# STM32.net
KiCad netlist of a schematic drawn in Altium Designer
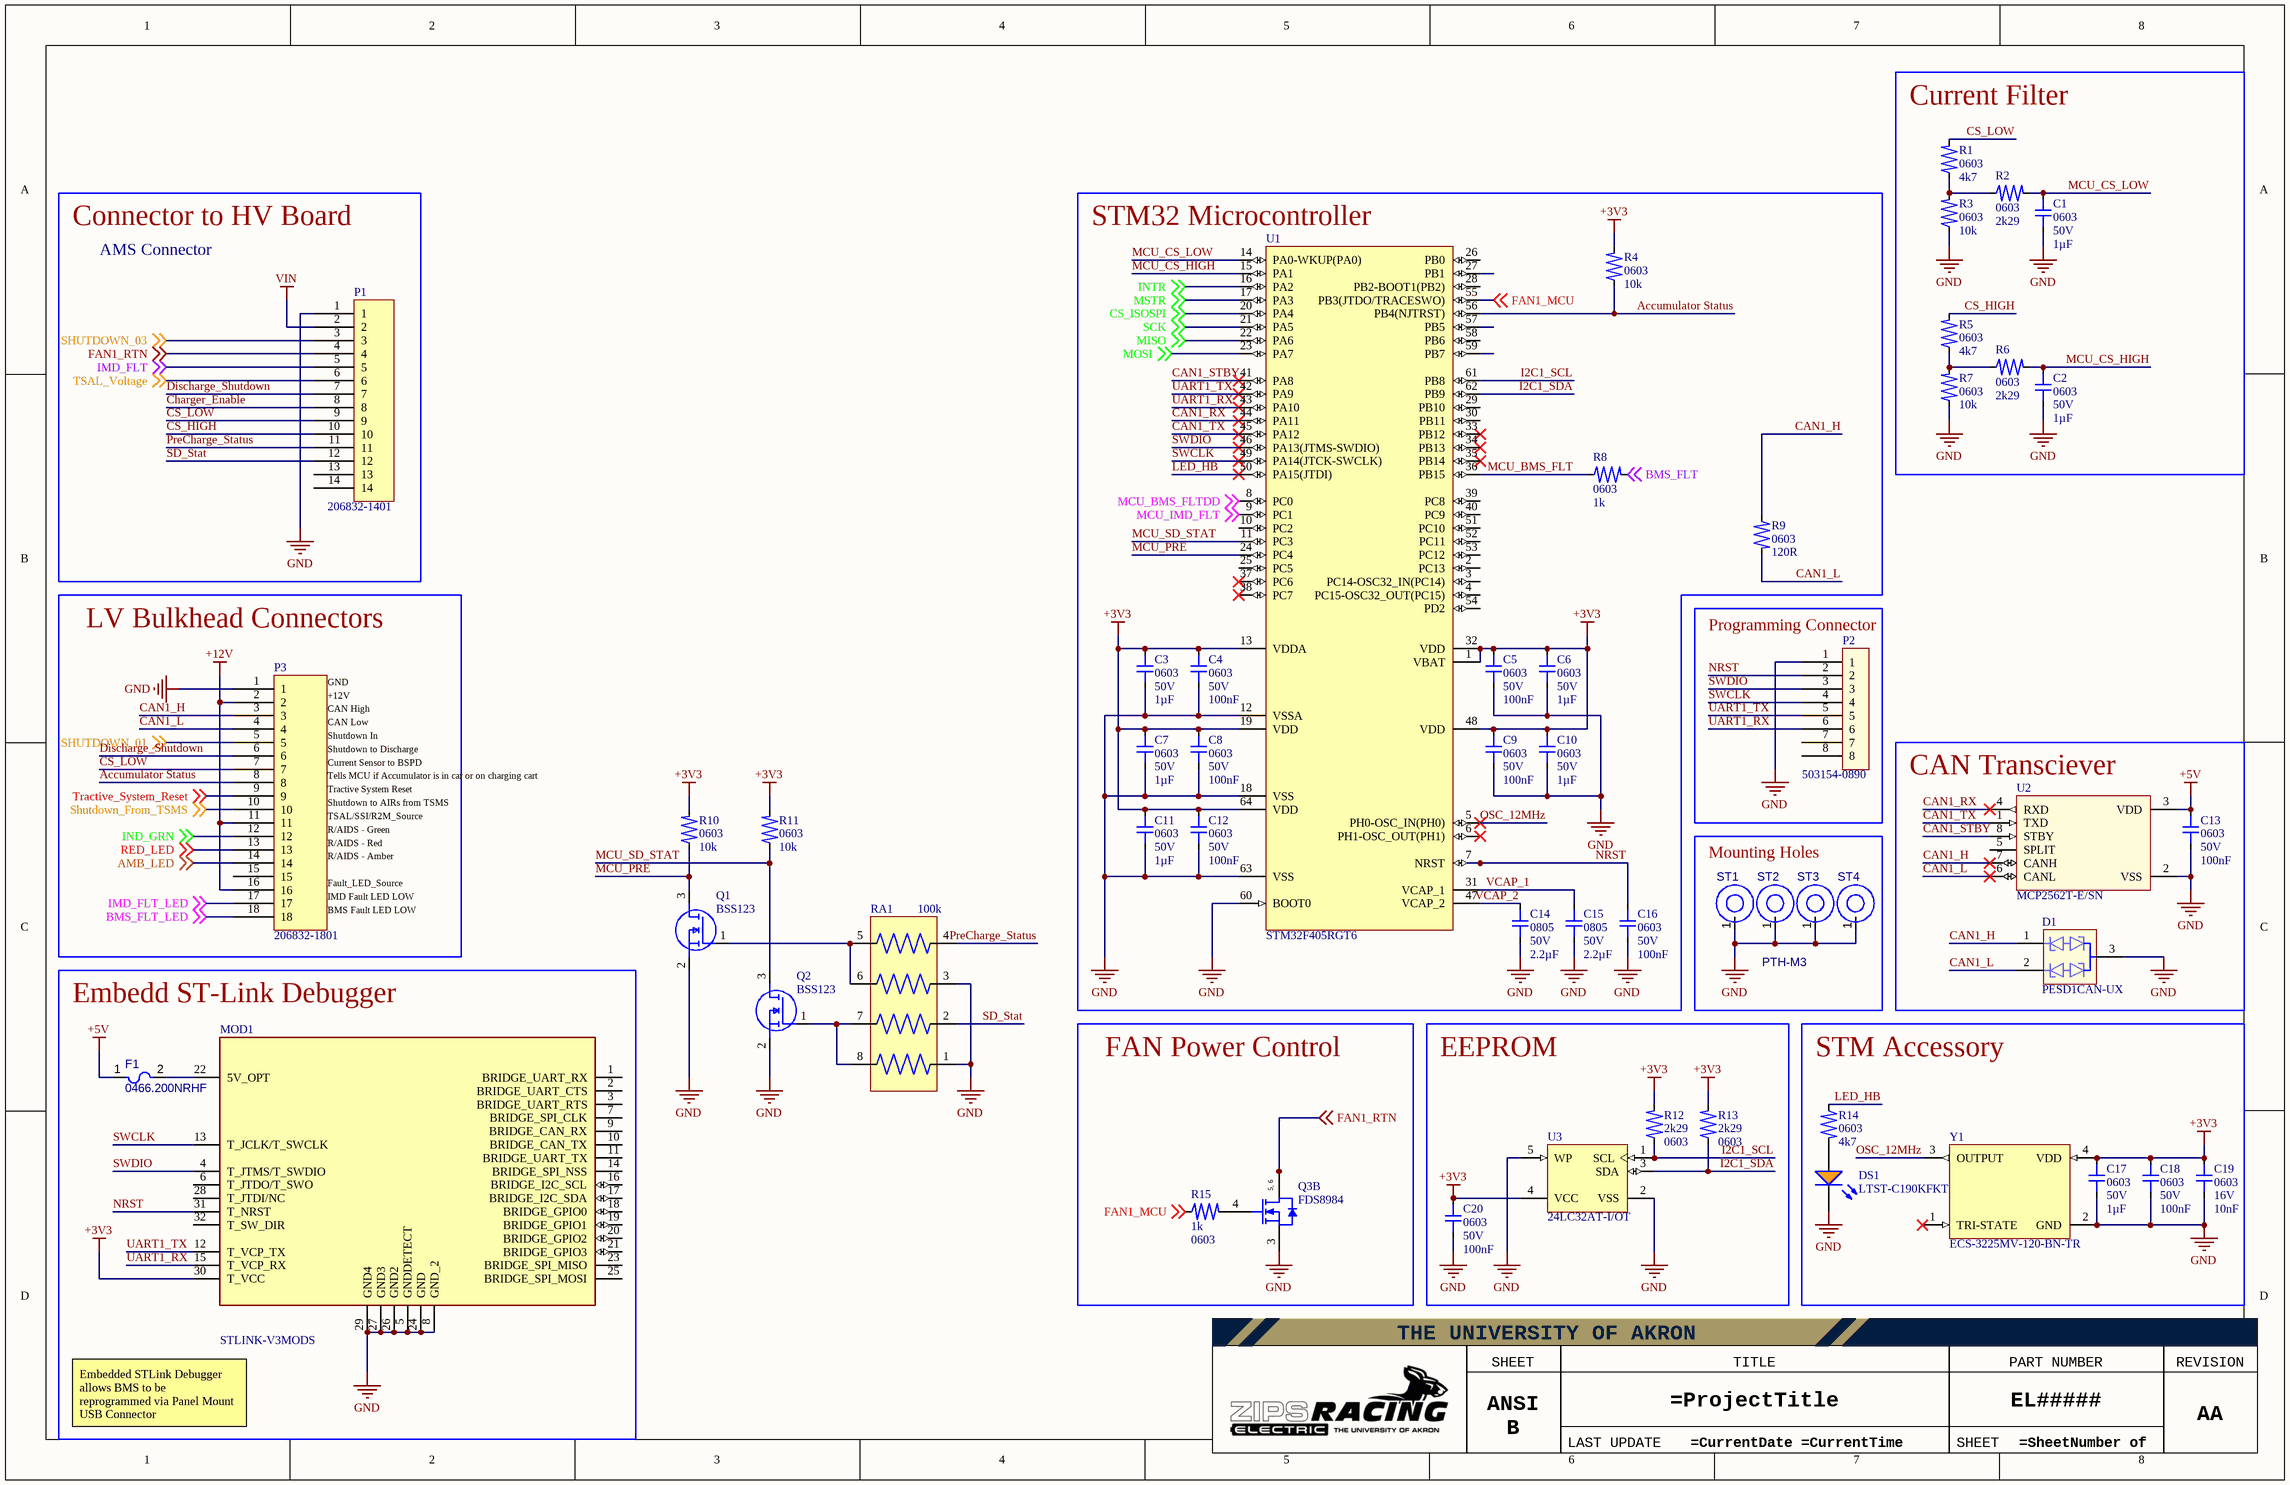
[diagram p0: STM32.SchDoc]

(export (version "E")
  (design (tool "Eeschema 10.0.6"))
  (components
    (comp (ref "C1")
      (value "1µF")
      (footprint "0603")
      (description "Capacitor, 0603, 5%")
      (fields (field (name "VOLTAGE") "50V") (field (name "Comment") "Capacitor 1uF 0603 5%"))
      (libsource (lib "Zips Racing Electric") (part "CAP-0603"))
    )
    (comp (ref "C2")
      (value "1µF")
      (footprint "0603")
      (description "Capacitor, 0603, 5%")
      (fields (field (name "VOLTAGE") "50V") (field (name "Comment") "Capacitor 1uF 0603 5%"))
      (libsource (lib "Zips Racing Electric") (part "CAP-0603"))
    )
    (comp (ref "C3")
      (value "1µF")
      (footprint "0603")
      (description "Capacitor, 0603, 5%")
      (fields (field (name "VOLTAGE") "50V") (field (name "Comment") "Capacitor 1uF 0603 5%"))
      (libsource (lib "Zips Racing Electric") (part "CAP-0603"))
    )
    (comp (ref "C4")
      (value "100nF")
      (footprint "0603")
      (description "Capacitor, 0603, 5%")
      (fields (field (name "VOLTAGE") "50V") (field (name "Comment") "Capacitor 100nF 0603 5%"))
      (libsource (lib "Zips Racing Electric") (part "CAP-0603"))
    )
    (comp (ref "C5")
      (value "100nF")
      (footprint "0603")
      (description "Capacitor, 0603, 5%")
      (fields (field (name "VOLTAGE") "50V") (field (name "Comment") "Capacitor 100nF 0603 5%"))
      (libsource (lib "Zips Racing Electric") (part "CAP-0603"))
    )
    (comp (ref "C6")
      (value "1µF")
      (footprint "0603")
      (description "Capacitor, 0603, 5%")
      (fields (field (name "VOLTAGE") "50V") (field (name "Comment") "Capacitor 1uF 0603 5%"))
      (libsource (lib "Zips Racing Electric") (part "CAP-0603"))
    )
    (comp (ref "C7")
      (value "1µF")
      (footprint "0603")
      (description "Capacitor, 0603, 5%")
      (fields (field (name "VOLTAGE") "50V") (field (name "Comment") "Capacitor 1uF 0603 5%"))
      (libsource (lib "Zips Racing Electric") (part "CAP-0603"))
    )
    (comp (ref "C8")
      (value "100nF")
      (footprint "0603")
      (description "Capacitor, 0603, 5%")
      (fields (field (name "VOLTAGE") "50V") (field (name "Comment") "Capacitor 100nF 0603 5%"))
      (libsource (lib "Zips Racing Electric") (part "CAP-0603"))
    )
    (comp (ref "C9")
      (value "100nF")
      (footprint "0603")
      (description "Capacitor, 0603, 5%")
      (fields (field (name "VOLTAGE") "50V") (field (name "Comment") "Capacitor 100nF 0603 5%"))
      (libsource (lib "Zips Racing Electric") (part "CAP-0603"))
    )
    (comp (ref "C10")
      (value "1µF")
      (footprint "0603")
      (description "Capacitor, 0603, 5%")
      (fields (field (name "VOLTAGE") "50V") (field (name "Comment") "Capacitor 1uF 0603 5%"))
      (libsource (lib "Zips Racing Electric") (part "CAP-0603"))
    )
    (comp (ref "C11")
      (value "1µF")
      (footprint "0603")
      (description "Capacitor, 0603, 5%")
      (fields (field (name "VOLTAGE") "50V") (field (name "Comment") "Capacitor 1uF 0603 5%"))
      (libsource (lib "Zips Racing Electric") (part "CAP-0603"))
    )
    (comp (ref "C12")
      (value "100nF")
      (footprint "0603")
      (description "Capacitor, 0603, 5%")
      (fields (field (name "VOLTAGE") "50V") (field (name "Comment") "Capacitor 100nF 0603 5%"))
      (libsource (lib "Zips Racing Electric") (part "CAP-0603"))
    )
    (comp (ref "C13")
      (value "100nF")
      (footprint "0603")
      (description "Capacitor, 0603, 5%")
      (fields (field (name "VOLTAGE") "50V") (field (name "Comment") "Capacitor 100nF 0603 5%"))
      (libsource (lib "Zips Racing Electric") (part "CAP-0603"))
    )
    (comp (ref "C14")
      (value "2.2µF")
      (footprint "0805")
      (description "Capacitor, 0805, 5%")
      (fields (field (name "VOLTAGE") "50V") (field (name "Comment") "Capacitor 2.2F 0805 5%"))
      (libsource (lib "Zips Racing Electric") (part "CAP-0603"))
    )
    (comp (ref "C15")
      (value "2.2µF")
      (footprint "0805")
      (description "Capacitor, 0805, 5%")
      (fields (field (name "VOLTAGE") "50V") (field (name "Comment") "Capacitor 2.2F 0805 5%"))
      (libsource (lib "Zips Racing Electric") (part "CAP-0603"))
    )
    (comp (ref "C16")
      (value "100nF")
      (footprint "0603")
      (description "Capacitor, 0603, 5%")
      (fields (field (name "VOLTAGE") "50V") (field (name "Comment") "Capacitor 100nF 0603 5%"))
      (libsource (lib "Zips Racing Electric") (part "CAP-0603"))
    )
    (comp (ref "C17")
      (value "1µF")
      (footprint "0603")
      (description "Capacitor, 0603, 5%")
      (fields (field (name "VOLTAGE") "50V") (field (name "Comment") "Capacitor 1uF 0603 5%"))
      (libsource (lib "Zips Racing Electric") (part "CAP-0603"))
    )
    (comp (ref "C18")
      (value "100nF")
      (footprint "0603")
      (description "Capacitor, 0603, 5%")
      (fields (field (name "VOLTAGE") "50V") (field (name "Comment") "Capacitor 100nF 0603 5%"))
      (libsource (lib "Zips Racing Electric") (part "CAP-0603"))
    )
    (comp (ref "C19")
      (value "10nF")
      (footprint "0603")
      (description "Capacitor, 0603, 5%")
      (fields (field (name "VOLTAGE") "16V") (field (name "Comment") "Capacitor 10nF 0603 5%"))
      (libsource (lib "Zips Racing Electric") (part "CAP-0603"))
    )
    (comp (ref "C20")
      (value "100nF")
      (footprint "0603")
      (description "Capacitor, 0603, 5%")
      (fields (field (name "VOLTAGE") "50V") (field (name "Comment") "Capacitor 100nF 0603 5%"))
      (libsource (lib "Zips Racing Electric") (part "CAP-0603"))
    )
    (comp (ref "D1")
      (value "PESD1CAN-UX")
      (footprint "FP-SOT323-MFG")
      (description "Trans Voltage Suppressor Diode, 150W, 24V V(RWM), Bidirectional, 2 Element, Silicon")
      (libsource (lib "Zips Racing Electric") (part "04d57993b6b7b0f5b3c95ba4f97dea0"))
    )
    (comp (ref "DS1")
      (value "LTST-C190KFKT")
      (footprint "LTST-C190KFKT_V")
      (description "LED Uni-Color Orange, 75 mW, 30 mA, -35 to 85 degC, 2-Pin SMD, RoHS, Tape and Reel")
      (fields (field (name "POWER") "75mW") (field (name "MANUFACTURER") "Lite-On"))
      (libsource (lib "Zips Racing Electric") (part "LED-ORANGE-AK-2"))
    )
    (comp (ref "F1")
      (value "0466.200NRHF")
      (footprint "FP-0466-MFG")
      (description "Electric Fuse, Very Fast Blow, 0.2A, 125VAC, 125VDC, 50A (IR), Supplemental, Surface Mount, 1206")
      (libsource (lib "Zips Racing Electric") (part "FUSE-2"))
    )
    (comp (ref "MOD1")
      (value "STLINK-V3MODS")
      (footprint "STLINK-V3MODS-Footprint-1")
      (description "STLINK V3 Debugger Board Module")
      (libsource (lib "Zips Racing Electric") (part "STLINK-V3MODS-Symbol-1"))
    )
    (comp (ref "P1")
      (value "206832-1401")
      (footprint "206832-1001-Footprint-1")
      (description "MICRO-FIT Plus Header Assembly Dual Row 10 Position Straight Tin")
      (libsource (lib "Zips Racing Electric") (part "206832-1401-Symbol-1"))
    )
    (comp (ref "P2")
      (value "503154-0890")
      (footprint "FP-503154-0890-MFG")
      (libsource (lib "Zips Racing Electric") (part "503154-0890-Symbol-1"))
    )
    (comp (ref "P3")
      (value "206832-1801")
      (footprint "MOLEX_2068321801")
      (libsource (lib "Zips Racing Electric") (part "206832-1801"))
    )
    (comp (ref "Q1")
      (value "BSS123")
      (footprint "SOT96P237X111-3N")
      (description "MOSFET N-CH 100V 170MA SOT23-3")
      (fields
        (field (name "MOUSER PART NUMBER") "512-BSS123")
        (field (name "SOURCE") "Zips_Racing_Electric.SchLib")
      )
      (libsource (lib "Zips Racing Electric") (part "BSS123"))
    )
    (comp (ref "Q2")
      (value "BSS123")
      (footprint "SOT96P237X111-3N")
      (description "MOSFET N-CH 100V 170MA SOT23-3")
      (fields
        (field (name "MOUSER PART NUMBER") "512-BSS123")
        (field (name "SOURCE") "Zips_Racing_Electric.SchLib")
      )
      (libsource (lib "Zips Racing Electric") (part "BSS123"))
    )
    (comp (ref "Q3")
      (value "FDS8984")
      (footprint "FAIR-SOIC-8_V")
      (libsource (lib "Zips Racing Electric") (part "NEMOS-SGDD-SGDD-8"))
    )
    (comp (ref "R1")
      (value "4k7")
      (footprint "0603")
      (description "Resistor, 0603, 1%, 1/10W")
      (fields (field (name "TOLERANCE") "1%") (field (name "POWER") "100mW"))
      (libsource (lib "Zips Racing Electric") (part "RES-0603"))
    )
    (comp (ref "R2")
      (value "2k29")
      (footprint "0603")
      (description "Resistor, 0603, 1%, 1/10W")
      (fields (field (name "TOLERANCE") "1%") (field (name "POWER") "100mW"))
      (libsource (lib "Zips Racing Electric") (part "RES-0603"))
    )
    (comp (ref "R3")
      (value "10k")
      (footprint "0603")
      (description "Resistor, 0603, 10k")
      (fields (field (name "TOLERANCE") "1%") (field (name "POWER") "100mW"))
      (libsource (lib "Zips Racing Electric") (part "RES-0603"))
    )
    (comp (ref "R4")
      (value "10k")
      (footprint "0603")
      (description "Resistor, 0603, 10k")
      (fields (field (name "TOLERANCE") "1%") (field (name "POWER") "100mW"))
      (libsource (lib "Zips Racing Electric") (part "RES-0603"))
    )
    (comp (ref "R5")
      (value "4k7")
      (footprint "0603")
      (description "Resistor, 0603, 1%, 1/10W")
      (fields (field (name "TOLERANCE") "1%") (field (name "POWER") "100mW"))
      (libsource (lib "Zips Racing Electric") (part "RES-0603"))
    )
    (comp (ref "R6")
      (value "2k29")
      (footprint "0603")
      (description "Resistor, 0603, 1%, 1/10W")
      (fields (field (name "TOLERANCE") "1%") (field (name "POWER") "100mW"))
      (libsource (lib "Zips Racing Electric") (part "RES-0603"))
    )
    (comp (ref "R7")
      (value "10k")
      (footprint "0603")
      (description "Resistor, 0603, 10k")
      (fields (field (name "TOLERANCE") "1%") (field (name "POWER") "100mW"))
      (libsource (lib "Zips Racing Electric") (part "RES-0603"))
    )
    (comp (ref "R8")
      (value "1k")
      (footprint "0603")
      (description "Resistor, 0603, 1k")
      (fields (field (name "POWER") "100mW") (field (name "TOLERANCE") "1%"))
      (libsource (lib "Zips Racing Electric") (part "RES-0603"))
    )
    (comp (ref "R9")
      (value "120R")
      (footprint "0603")
      (description "Resistor, 0603, 1%, 1/10W")
      (fields (field (name "TOLERANCE") "1%") (field (name "POWER") "100mW"))
      (libsource (lib "Zips Racing Electric") (part "RES-0603"))
    )
    (comp (ref "R10")
      (value "10k")
      (footprint "0603")
      (description "Resistor, 0603, 10k")
      (fields (field (name "TOLERANCE") "1%") (field (name "POWER") "100mW"))
      (libsource (lib "Zips Racing Electric") (part "RES-0603"))
    )
    (comp (ref "R11")
      (value "10k")
      (footprint "0603")
      (description "Resistor, 0603, 10k")
      (fields (field (name "TOLERANCE") "1%") (field (name "POWER") "100mW"))
      (libsource (lib "Zips Racing Electric") (part "RES-0603"))
    )
    (comp (ref "R12")
      (value "2k29")
      (footprint "0603")
      (description "Resistor, 0603, 1%, 1/10W")
      (fields (field (name "TOLERANCE") "1%") (field (name "POWER") "100mW"))
      (libsource (lib "Zips Racing Electric") (part "RES-0603"))
    )
    (comp (ref "R13")
      (value "2k29")
      (footprint "0603")
      (description "Resistor, 0603, 1%, 1/10W")
      (fields (field (name "TOLERANCE") "1%") (field (name "POWER") "100mW"))
      (libsource (lib "Zips Racing Electric") (part "RES-0603"))
    )
    (comp (ref "R14")
      (value "4k7")
      (footprint "0603")
      (description "Resistor, 0603, 1%, 1/10W")
      (fields (field (name "TOLERANCE") "1%") (field (name "POWER") "100mW"))
      (libsource (lib "Zips Racing Electric") (part "RES-0603"))
    )
    (comp (ref "R15")
      (value "1k")
      (footprint "0603")
      (description "Resistor, 0603, 1k")
      (fields (field (name "POWER") "100mW") (field (name "TOLERANCE") "1%"))
      (libsource (lib "Zips Racing Electric") (part "RES-0603"))
    )
    (comp (ref "RA1")
      (value "100k")
      (footprint "New footprint 1")
      (fields (field (name "TOLERANCE") "5%") (field (name "Comment") "YC164-JR-07100KL"))
      (libsource (lib "Zips Racing Electric") (part "YC164-JR-07100KL-Symbol-1"))
    )
    (comp (ref "ST1")
      (value "PTH-M3")
      (footprint "PTH-M2D5X5")
      (description "M3 Plated Thru-Hole  (3.2mm), 7mm pad, 10 mm keep out zone")
      (libsource (lib "Zips Racing Electric") (part "CMP-00028-00000-1"))
    )
    (comp (ref "ST2")
      (value "PTH-M3")
      (footprint "PTH-M2D5X5")
      (description "M3 Plated Thru-Hole  (3.2mm), 7mm pad, 10 mm keep out zone")
      (libsource (lib "Zips Racing Electric") (part "CMP-00028-00000-1"))
    )
    (comp (ref "ST3")
      (value "PTH-M3")
      (footprint "PTH-M2D5X5")
      (description "M3 Plated Thru-Hole  (3.2mm), 7mm pad, 10 mm keep out zone")
      (libsource (lib "Zips Racing Electric") (part "CMP-00028-00000-1"))
    )
    (comp (ref "ST4")
      (value "PTH-M3")
      (footprint "PTH-M2D5X5")
      (description "M3 Plated Thru-Hole  (3.2mm), 7mm pad, 10 mm keep out zone")
      (libsource (lib "Zips Racing Electric") (part "CMP-00028-00000-1"))
    )
    (comp (ref "U1")
      (value "STM32F405RGT6")
      (footprint "STM-LQFP64_V")
      (description "RISC Microcontroller, 32-Bit, FLASH, CORTEX-M4 CPU, 168MHz, CMOS, PQFP64")
      (libsource (lib "Zips Racing Electric") (part "MC-ARM-STM32F4X5-SQ64"))
    )
    (comp (ref "U2")
      (value "MCP2562T-E/SN")
      (footprint "MCP2562T-E_SN-Footprint-1")
      (description "IC TXRX CAN 8SOIC")
      (libsource (lib "Zips Racing Electric") (part "MCP2562T-E_SN-Symbol-1"))
    )
    (comp (ref "U3")
      (value "24LC32AT-I/OT")
      (footprint "SOT-23-OT5_L")
      (description "EEPROM, 4KX8, Serial, CMOS, PDSO5")
      (libsource (lib "Zips Racing Electric") (part "MEM-SEEPROM-24AA16-OT-5"))
    )
    (comp (ref "Y1")
      (value "ECS-3225MV-120-BN-TR")
      (footprint "ECS-3225MV-120-BN-TR-Footprint-1")
      (description "HCMOS Output Clock Oscillator, 12MHz Nom")
      (libsource (lib "Zips Racing Electric") (part "ECS-3225MV-120-BN-TR-Symbol-1"))
    )
  )
  (nets
    (net (code "1") (name "+3V3") (class "Default")
      (node (ref "C10") (pin "2") (pinfunction "2_2") (pintype "passive"))
      (node (ref "C11") (pin "2") (pinfunction "2_2") (pintype "passive"))
      (node (ref "C12") (pin "2") (pinfunction "2_2") (pintype "passive"))
      (node (ref "C17") (pin "2") (pinfunction "2_2") (pintype "passive"))
      (node (ref "C18") (pin "2") (pinfunction "2_2") (pintype "passive"))
      (node (ref "C19") (pin "2") (pinfunction "2_2") (pintype "passive"))
      (node (ref "C20") (pin "2") (pinfunction "2_2") (pintype "passive"))
      (node (ref "C3") (pin "2") (pinfunction "2_2") (pintype "passive"))
      (node (ref "C4") (pin "2") (pinfunction "2_2") (pintype "passive"))
      (node (ref "C5") (pin "2") (pinfunction "2_2") (pintype "passive"))
      (node (ref "C6") (pin "2") (pinfunction "2_2") (pintype "passive"))
      (node (ref "C7") (pin "2") (pinfunction "2_2") (pintype "passive"))
      (node (ref "C8") (pin "2") (pinfunction "2_2") (pintype "passive"))
      (node (ref "C9") (pin "2") (pinfunction "2_2") (pintype "passive"))
      (node (ref "MOD1") (pin "30") (pinfunction "T_VCC_30") (pintype "passive"))
      (node (ref "R10") (pin "2") (pinfunction "2_2") (pintype "passive"))
      (node (ref "R11") (pin "2") (pinfunction "2_2") (pintype "passive"))
      (node (ref "R12") (pin "2") (pinfunction "2_2") (pintype "passive"))
      (node (ref "R13") (pin "2") (pinfunction "2_2") (pintype "passive"))
      (node (ref "R4") (pin "2") (pinfunction "2_2") (pintype "passive"))
      (node (ref "U1") (pin "1") (pinfunction "VBAT_1") (pintype "power_in"))
      (node (ref "U1") (pin "13") (pinfunction "VDDA_13") (pintype "power_in"))
      (node (ref "U1") (pin "19") (pinfunction "VDD_19") (pintype "power_in"))
      (node (ref "U1") (pin "32") (pinfunction "VDD_32") (pintype "power_in"))
      (node (ref "U1") (pin "48") (pinfunction "VDD_48") (pintype "power_in"))
      (node (ref "U1") (pin "64") (pinfunction "VDD_64") (pintype "power_in"))
      (node (ref "U3") (pin "4") (pinfunction "VCC_4") (pintype "power_in"))
      (node (ref "Y1") (pin "4") (pinfunction "VDD_4") (pintype "input"))
    )
    (net (code "2") (name "+5V") (class "Default")
      (node (ref "C13") (pin "2") (pinfunction "2_2") (pintype "passive"))
      (node (ref "F1") (pin "1") (pinfunction "1_1") (pintype "passive"))
      (node (ref "U2") (pin "3") (pinfunction "VDD_3") (pintype "power_in"))
    )
    (net (code "3") (name "+12V") (class "Default")
      (node (ref "P3") (pin "11") (pinfunction "11_11") (pintype "passive"))
      (node (ref "P3") (pin "16") (pinfunction "16_16") (pintype "passive"))
      (node (ref "P3") (pin "2") (pinfunction "2_2") (pintype "passive"))
    )
    (net (code "4") (name "/Accumulator Status") (class "Default")
      (node (ref "P3") (pin "8") (pinfunction "8_8") (pintype "passive"))
      (node (ref "R4") (pin "1") (pinfunction "1_1") (pintype "passive"))
      (node (ref "U1") (pin "56") (pinfunction "PB4(NJTRST)_56") (pintype "bidirectional"))
    )
    (net (code "5") (name "/CAN1_H") (class "Default")
      (node (ref "D1") (pin "1") (pinfunction "cathode_1_1") (pintype "passive"))
      (node (ref "P3") (pin "3") (pinfunction "3_3") (pintype "passive"))
      (node (ref "R9") (pin "1") (pinfunction "1_1") (pintype "passive"))
      (node (ref "U2") (pin "7") (pinfunction "CANH_7") (pintype "bidirectional"))
    )
    (net (code "6") (name "/CAN1_L") (class "Default")
      (node (ref "D1") (pin "2") (pinfunction "cathode_2_2") (pintype "passive"))
      (node (ref "P3") (pin "4") (pinfunction "4_4") (pintype "passive"))
      (node (ref "R9") (pin "2") (pinfunction "2_2") (pintype "passive"))
      (node (ref "U2") (pin "6") (pinfunction "CANL_6") (pintype "bidirectional"))
    )
    (net (code "7") (name "/CAN1_RX") (class "Default")
      (node (ref "U1") (pin "44") (pinfunction "PA11_44") (pintype "bidirectional"))
      (node (ref "U2") (pin "4") (pinfunction "RXD_4") (pintype "output"))
    )
    (net (code "8") (name "/CAN1_STBY") (class "Default")
      (node (ref "U1") (pin "41") (pinfunction "PA8_41") (pintype "bidirectional"))
      (node (ref "U2") (pin "8") (pinfunction "STBY_8") (pintype "input"))
    )
    (net (code "9") (name "/CAN1_TX") (class "Default")
      (node (ref "U1") (pin "45") (pinfunction "PA12_45") (pintype "bidirectional"))
      (node (ref "U2") (pin "1") (pinfunction "TXD_1") (pintype "input"))
    )
    (net (code "10") (name "/CS_HIGH") (class "Default")
      (node (ref "P1") (pin "10") (pinfunction "10_10") (pintype "passive"))
      (node (ref "R5") (pin "2") (pinfunction "2_2") (pintype "passive"))
    )
    (net (code "11") (name "/CS_LOW") (class "Default")
      (node (ref "P1") (pin "9") (pinfunction "9_9") (pintype "passive"))
      (node (ref "P3") (pin "7") (pinfunction "7_7") (pintype "passive"))
      (node (ref "R1") (pin "2") (pinfunction "2_2") (pintype "passive"))
    )
    (net (code "12") (name "/Charger_Enable") (class "Default")
      (node (ref "P1") (pin "8") (pinfunction "8_8") (pintype "passive"))
    )
    (net (code "13") (name "/Discharge_Shutdown") (class "Default")
      (node (ref "P1") (pin "7") (pinfunction "7_7") (pintype "passive"))
      (node (ref "P3") (pin "6") (pinfunction "6_6") (pintype "passive"))
    )
    (net (code "14") (name "/I2C1_SCL") (class "Default")
      (node (ref "R12") (pin "1") (pinfunction "1_1") (pintype "passive"))
      (node (ref "U1") (pin "61") (pinfunction "PB8_61") (pintype "bidirectional"))
      (node (ref "U3") (pin "1") (pinfunction "SCL_1") (pintype "input"))
    )
    (net (code "15") (name "/I2C1_SDA") (class "Default")
      (node (ref "R13") (pin "1") (pinfunction "1_1") (pintype "passive"))
      (node (ref "U1") (pin "62") (pinfunction "PB9_62") (pintype "bidirectional"))
      (node (ref "U3") (pin "3") (pinfunction "SDA_3") (pintype "bidirectional"))
    )
    (net (code "16") (name "/LED_HB") (class "Default")
      (node (ref "R14") (pin "1") (pinfunction "1_1") (pintype "passive"))
      (node (ref "U1") (pin "50") (pinfunction "PA15(JTDI)_50") (pintype "bidirectional"))
    )
    (net (code "17") (name "/MCU_BMS_FLT") (class "Default")
      (node (ref "R8") (pin "1") (pinfunction "1_1") (pintype "passive"))
      (node (ref "U1") (pin "36") (pinfunction "PB15_36") (pintype "bidirectional"))
    )
    (net (code "18") (name "/MCU_CS_HIGH") (class "Default")
      (node (ref "C2") (pin "2") (pinfunction "2_2") (pintype "passive"))
      (node (ref "R6") (pin "2") (pinfunction "2_2") (pintype "passive"))
      (node (ref "U1") (pin "15") (pinfunction "PA1_15") (pintype "bidirectional"))
    )
    (net (code "19") (name "/MCU_CS_LOW") (class "Default")
      (node (ref "C1") (pin "2") (pinfunction "2_2") (pintype "passive"))
      (node (ref "R2") (pin "2") (pinfunction "2_2") (pintype "passive"))
      (node (ref "U1") (pin "14") (pinfunction "PA0-WKUP(PA0)_14") (pintype "bidirectional"))
    )
    (net (code "20") (name "/MCU_PRE") (class "Default")
      (node (ref "Q1") (pin "3") (pinfunction "D_3") (pintype "passive"))
      (node (ref "R10") (pin "1") (pinfunction "1_1") (pintype "passive"))
      (node (ref "U1") (pin "24") (pinfunction "PC4_24") (pintype "bidirectional"))
    )
    (net (code "21") (name "/MCU_SD_STAT") (class "Default")
      (node (ref "Q2") (pin "3") (pinfunction "D_3") (pintype "passive"))
      (node (ref "R11") (pin "1") (pinfunction "1_1") (pintype "passive"))
      (node (ref "U1") (pin "11") (pinfunction "PC3_11") (pintype "bidirectional"))
    )
    (net (code "22") (name "/NRST") (class "Default")
      (node (ref "C16") (pin "2") (pinfunction "2_2") (pintype "passive"))
      (node (ref "MOD1") (pin "31") (pinfunction "T_NRST_31") (pintype "passive"))
      (node (ref "P2") (pin "2") (pinfunction "2_2") (pintype "passive"))
      (node (ref "U1") (pin "7") (pinfunction "NRST_7") (pintype "bidirectional"))
    )
    (net (code "23") (name "/OSC_12MHz") (class "Default")
      (node (ref "U1") (pin "5") (pinfunction "PH0-OSC_IN(PH0)_5") (pintype "bidirectional"))
      (node (ref "Y1") (pin "3") (pinfunction "OUTPUT_3") (pintype "output"))
    )
    (net (code "24") (name "/PreCharge_Status") (class "Default")
      (node (ref "P1") (pin "11") (pinfunction "11_11") (pintype "passive"))
      (node (ref "RA1") (pin "4") (pinfunction "4_4") (pintype "passive"))
    )
    (net (code "25") (name "/SD_Stat") (class "Default")
      (node (ref "P1") (pin "12") (pinfunction "12_12") (pintype "passive"))
      (node (ref "RA1") (pin "2") (pinfunction "2_2") (pintype "passive"))
    )
    (net (code "26") (name "/SWCLK") (class "Default")
      (node (ref "MOD1") (pin "13") (pinfunction "T_JCLK/T_SWCLK_13") (pintype "passive"))
      (node (ref "P2") (pin "4") (pinfunction "4_4") (pintype "passive"))
      (node (ref "U1") (pin "49") (pinfunction "PA14(JTCK-SWCLK)_49") (pintype "bidirectional"))
    )
    (net (code "27") (name "/SWDIO") (class "Default")
      (node (ref "MOD1") (pin "4") (pinfunction "T_JTMS/T_SWDIO_4") (pintype "passive"))
      (node (ref "P2") (pin "3") (pinfunction "3_3") (pintype "passive"))
      (node (ref "U1") (pin "46") (pinfunction "PA13(JTMS-SWDIO)_46") (pintype "bidirectional"))
    )
    (net (code "28") (name "/UART1_RX") (class "Default")
      (node (ref "MOD1") (pin "15") (pinfunction "T_VCP_RX_15") (pintype "passive"))
      (node (ref "P2") (pin "6") (pinfunction "6_6") (pintype "passive"))
      (node (ref "U1") (pin "43") (pinfunction "PA10_43") (pintype "bidirectional"))
    )
    (net (code "29") (name "/UART1_TX") (class "Default")
      (node (ref "MOD1") (pin "12") (pinfunction "T_VCP_TX_12") (pintype "passive"))
      (node (ref "P2") (pin "5") (pinfunction "5_5") (pintype "passive"))
      (node (ref "U1") (pin "42") (pinfunction "PA9_42") (pintype "bidirectional"))
    )
    (net (code "30") (name "/VCAP_1") (class "Default")
      (node (ref "C15") (pin "2") (pinfunction "2_2") (pintype "passive"))
      (node (ref "U1") (pin "31") (pinfunction "VCAP_1_31") (pintype "power_in"))
    )
    (net (code "31") (name "/VCAP_2") (class "Default")
      (node (ref "C14") (pin "2") (pinfunction "2_2") (pintype "passive"))
      (node (ref "U1") (pin "47") (pinfunction "VCAP_2_47") (pintype "power_in"))
    )
    (net (code "32") (name "AMB_LED") (class "Default")
      (node (ref "P3") (pin "14") (pinfunction "14_14") (pintype "passive"))
    )
    (net (code "33") (name "BMS_FLT") (class "Default")
      (node (ref "R8") (pin "2") (pinfunction "2_2") (pintype "passive"))
    )
    (net (code "34") (name "BMS_FLT_LED") (class "Default")
      (node (ref "P3") (pin "18") (pinfunction "18_18") (pintype "passive"))
    )
    (net (code "35") (name "CS_ISOSPI") (class "Default")
      (node (ref "U1") (pin "20") (pinfunction "PA4_20") (pintype "bidirectional"))
    )
    (net (code "36") (name "FAN1_MCU") (class "Default")
      (node (ref "R15") (pin "1") (pinfunction "1_1") (pintype "passive"))
      (node (ref "U1") (pin "55") (pinfunction "PB3(JTDO/TRACESWO)_55") (pintype "bidirectional"))
    )
    (net (code "37") (name "FAN1_RTN") (class "Default")
      (node (ref "P1") (pin "4") (pinfunction "4_4") (pintype "passive"))
      (node (ref "Q3") (pin "5") (pinfunction "D2_5") (pintype "passive"))
      (node (ref "Q3") (pin "6") (pinfunction "D2_6") (pintype "passive"))
    )
    (net (code "38") (name "GND") (class "Default")
      (node (ref "C1") (pin "1") (pinfunction "1_1") (pintype "passive"))
      (node (ref "C10") (pin "1") (pinfunction "1_1") (pintype "passive"))
      (node (ref "C11") (pin "1") (pinfunction "1_1") (pintype "passive"))
      (node (ref "C12") (pin "1") (pinfunction "1_1") (pintype "passive"))
      (node (ref "C13") (pin "1") (pinfunction "1_1") (pintype "passive"))
      (node (ref "C14") (pin "1") (pinfunction "1_1") (pintype "passive"))
      (node (ref "C15") (pin "1") (pinfunction "1_1") (pintype "passive"))
      (node (ref "C16") (pin "1") (pinfunction "1_1") (pintype "passive"))
      (node (ref "C17") (pin "1") (pinfunction "1_1") (pintype "passive"))
      (node (ref "C18") (pin "1") (pinfunction "1_1") (pintype "passive"))
      (node (ref "C19") (pin "1") (pinfunction "1_1") (pintype "passive"))
      (node (ref "C2") (pin "1") (pinfunction "1_1") (pintype "passive"))
      (node (ref "C20") (pin "1") (pinfunction "1_1") (pintype "passive"))
      (node (ref "C3") (pin "1") (pinfunction "1_1") (pintype "passive"))
      (node (ref "C4") (pin "1") (pinfunction "1_1") (pintype "passive"))
      (node (ref "C5") (pin "1") (pinfunction "1_1") (pintype "passive"))
      (node (ref "C6") (pin "1") (pinfunction "1_1") (pintype "passive"))
      (node (ref "C7") (pin "1") (pinfunction "1_1") (pintype "passive"))
      (node (ref "C8") (pin "1") (pinfunction "1_1") (pintype "passive"))
      (node (ref "C9") (pin "1") (pinfunction "1_1") (pintype "passive"))
      (node (ref "D1") (pin "3") (pinfunction "common_cathode_3") (pintype "passive"))
      (node (ref "DS1") (pin "2") (pinfunction "K_2") (pintype "passive"))
      (node (ref "MOD1") (pin "24") (pinfunction "GND_24") (pintype "power_in"))
      (node (ref "MOD1") (pin "26") (pinfunction "GND2_26") (pintype "power_in"))
      (node (ref "MOD1") (pin "27") (pinfunction "GND3_27") (pintype "power_in"))
      (node (ref "MOD1") (pin "29") (pinfunction "GND4_29") (pintype "power_in"))
      (node (ref "MOD1") (pin "5") (pinfunction "GNDDETECT_5") (pintype "power_in"))
      (node (ref "MOD1") (pin "8") (pinfunction "GND_2_8") (pintype "power_in"))
      (node (ref "P1") (pin "1") (pinfunction "1_1") (pintype "passive"))
      (node (ref "P2") (pin "1") (pinfunction "1_1") (pintype "passive"))
      (node (ref "P3") (pin "1") (pinfunction "1_1") (pintype "passive"))
      (node (ref "Q1") (pin "2") (pinfunction "S_2") (pintype "passive"))
      (node (ref "Q2") (pin "2") (pinfunction "S_2") (pintype "passive"))
      (node (ref "Q3") (pin "3") (pinfunction "S2_3") (pintype "passive"))
      (node (ref "R3") (pin "1") (pinfunction "1_1") (pintype "passive"))
      (node (ref "R7") (pin "1") (pinfunction "1_1") (pintype "passive"))
      (node (ref "RA1") (pin "1") (pinfunction "1_1") (pintype "passive"))
      (node (ref "RA1") (pin "3") (pinfunction "3_3") (pintype "passive"))
      (node (ref "ST1") (pin "1") (pinfunction "H1_1") (pintype "passive"))
      (node (ref "ST2") (pin "1") (pinfunction "H1_1") (pintype "passive"))
      (node (ref "ST3") (pin "1") (pinfunction "H1_1") (pintype "passive"))
      (node (ref "ST4") (pin "1") (pinfunction "H1_1") (pintype "passive"))
      (node (ref "U1") (pin "12") (pinfunction "VSSA_12") (pintype "power_in"))
      (node (ref "U1") (pin "18") (pinfunction "VSS_18") (pintype "power_in"))
      (node (ref "U1") (pin "60") (pinfunction "BOOT0_60") (pintype "input"))
      (node (ref "U1") (pin "63") (pinfunction "VSS_63") (pintype "power_in"))
      (node (ref "U2") (pin "2") (pinfunction "VSS_2") (pintype "power_in"))
      (node (ref "U3") (pin "2") (pinfunction "VSS_2") (pintype "power_in"))
      (node (ref "U3") (pin "5") (pinfunction "WP_5") (pintype "input"))
      (node (ref "Y1") (pin "2") (pinfunction "GND_2") (pintype "power_in"))
    )
    (net (code "39") (name "IMD_FLT") (class "Default")
      (node (ref "P1") (pin "5") (pinfunction "5_5") (pintype "passive"))
    )
    (net (code "40") (name "IMD_FLT_LED") (class "Default")
      (node (ref "P3") (pin "17") (pinfunction "17_17") (pintype "passive"))
    )
    (net (code "41") (name "IND_GRN") (class "Default")
      (node (ref "P3") (pin "12") (pinfunction "12_12") (pintype "passive"))
    )
    (net (code "42") (name "INTR") (class "Default")
      (node (ref "U1") (pin "16") (pinfunction "PA2_16") (pintype "bidirectional"))
    )
    (net (code "43") (name "MCU_BMS_FLTDD") (class "Default")
      (node (ref "U1") (pin "8") (pinfunction "PC0_8") (pintype "bidirectional"))
    )
    (net (code "44") (name "MCU_IMD_FLT") (class "Default")
      (node (ref "U1") (pin "9") (pinfunction "PC1_9") (pintype "bidirectional"))
    )
    (net (code "45") (name "MISO") (class "Default")
      (node (ref "U1") (pin "22") (pinfunction "PA6_22") (pintype "bidirectional"))
    )
    (net (code "46") (name "MOSI") (class "Default")
      (node (ref "U1") (pin "23") (pinfunction "PA7_23") (pintype "bidirectional"))
    )
    (net (code "47") (name "MSTR") (class "Default")
      (node (ref "U1") (pin "17") (pinfunction "PA3_17") (pintype "bidirectional"))
    )
    (net (code "48") (name "Net-(DS1-A)") (class "Default")
      (node (ref "DS1") (pin "1") (pinfunction "A_1") (pintype "passive"))
      (node (ref "R14") (pin "2") (pinfunction "2_2") (pintype "passive"))
    )
    (net (code "49") (name "Net-(MOD1-5V_OPT)") (class "Default")
      (node (ref "F1") (pin "2") (pinfunction "2_2") (pintype "passive"))
      (node (ref "MOD1") (pin "22") (pinfunction "5V_OPT_22") (pintype "passive"))
    )
    (net (code "50") (name "Net-(Q1-G)") (class "Default")
      (node (ref "Q1") (pin "1") (pinfunction "G_1") (pintype "passive"))
      (node (ref "RA1") (pin "5") (pinfunction "5_5") (pintype "passive"))
      (node (ref "RA1") (pin "6") (pinfunction "6_6") (pintype "passive"))
    )
    (net (code "51") (name "Net-(Q2-G)") (class "Default")
      (node (ref "Q2") (pin "1") (pinfunction "G_1") (pintype "passive"))
      (node (ref "RA1") (pin "7") (pinfunction "7_7") (pintype "passive"))
      (node (ref "RA1") (pin "8") (pinfunction "8_8") (pintype "passive"))
    )
    (net (code "52") (name "Net-(Q3B-G2)") (class "Default")
      (node (ref "Q3") (pin "4") (pinfunction "G2_4") (pintype "passive"))
      (node (ref "R15") (pin "2") (pinfunction "2_2") (pintype "passive"))
    )
    (net (code "53") (name "Net-(R1-Pad1)") (class "Default")
      (node (ref "R1") (pin "1") (pinfunction "1_1") (pintype "passive"))
      (node (ref "R2") (pin "1") (pinfunction "1_1") (pintype "passive"))
      (node (ref "R3") (pin "2") (pinfunction "2_2") (pintype "passive"))
    )
    (net (code "54") (name "Net-(R5-Pad1)") (class "Default")
      (node (ref "R5") (pin "1") (pinfunction "1_1") (pintype "passive"))
      (node (ref "R6") (pin "1") (pinfunction "1_1") (pintype "passive"))
      (node (ref "R7") (pin "2") (pinfunction "2_2") (pintype "passive"))
    )
    (net (code "55") (name "RED_LED") (class "Default")
      (node (ref "P3") (pin "13") (pinfunction "13_13") (pintype "passive"))
    )
    (net (code "56") (name "SCK") (class "Default")
      (node (ref "U1") (pin "21") (pinfunction "PA5_21") (pintype "bidirectional"))
    )
    (net (code "57") (name "SHUTDOWN_01") (class "Default")
      (node (ref "P3") (pin "5") (pinfunction "5_5") (pintype "passive"))
    )
    (net (code "58") (name "SHUTDOWN_03") (class "Default")
      (node (ref "P1") (pin "3") (pinfunction "3_3") (pintype "passive"))
    )
    (net (code "59") (name "Shutdown_From_TSMS") (class "Default")
      (node (ref "P3") (pin "10") (pinfunction "10_10") (pintype "passive"))
    )
    (net (code "60") (name "TSAL_Voltage") (class "Default")
      (node (ref "P1") (pin "6") (pinfunction "6_6") (pintype "passive"))
    )
    (net (code "61") (name "Tractive_System_Reset") (class "Default")
      (node (ref "P3") (pin "9") (pinfunction "9_9") (pintype "passive"))
    )
    (net (code "62") (name "VIN") (class "Default")
      (node (ref "P1") (pin "2") (pinfunction "2_2") (pintype "passive"))
    )
    (net (code "63") (name "unconnected-(MOD1-BRIDGE_CAN_RX-Pad9)") (class "Default")
      (node (ref "MOD1") (pin "9") (pinfunction "BRIDGE_CAN_RX_9") (pintype "passive"))
    )
    (net (code "64") (name "unconnected-(MOD1-BRIDGE_CAN_TX-Pad10)") (class "Default")
      (node (ref "MOD1") (pin "10") (pinfunction "BRIDGE_CAN_TX_10") (pintype "passive"))
    )
    (net (code "65") (name "unconnected-(MOD1-BRIDGE_GPIO0-Pad18)") (class "Default")
      (node (ref "MOD1") (pin "18") (pinfunction "BRIDGE_GPIO0_18") (pintype "bidirectional"))
    )
    (net (code "66") (name "unconnected-(MOD1-BRIDGE_GPIO1-Pad19)") (class "Default")
      (node (ref "MOD1") (pin "19") (pinfunction "BRIDGE_GPIO1_19") (pintype "bidirectional"))
    )
    (net (code "67") (name "unconnected-(MOD1-BRIDGE_GPIO2-Pad20)") (class "Default")
      (node (ref "MOD1") (pin "20") (pinfunction "BRIDGE_GPIO2_20") (pintype "bidirectional"))
    )
    (net (code "68") (name "unconnected-(MOD1-BRIDGE_GPIO3-Pad21)") (class "Default")
      (node (ref "MOD1") (pin "21") (pinfunction "BRIDGE_GPIO3_21") (pintype "bidirectional"))
    )
    (net (code "69") (name "unconnected-(MOD1-BRIDGE_I2C_SCL-Pad16)") (class "Default")
      (node (ref "MOD1") (pin "16") (pinfunction "BRIDGE_I2C_SCL_16") (pintype "bidirectional"))
    )
    (net (code "70") (name "unconnected-(MOD1-BRIDGE_I2C_SDA-Pad17)") (class "Default")
      (node (ref "MOD1") (pin "17") (pinfunction "BRIDGE_I2C_SDA_17") (pintype "bidirectional"))
    )
    (net (code "71") (name "unconnected-(MOD1-BRIDGE_SPI_CLK-Pad7)") (class "Default")
      (node (ref "MOD1") (pin "7") (pinfunction "BRIDGE_SPI_CLK_7") (pintype "passive"))
    )
    (net (code "72") (name "unconnected-(MOD1-BRIDGE_SPI_MISO-Pad23)") (class "Default")
      (node (ref "MOD1") (pin "23") (pinfunction "BRIDGE_SPI_MISO_23") (pintype "passive"))
    )
    (net (code "73") (name "unconnected-(MOD1-BRIDGE_SPI_MOSI-Pad25)") (class "Default")
      (node (ref "MOD1") (pin "25") (pinfunction "BRIDGE_SPI_MOSI_25") (pintype "passive"))
    )
    (net (code "74") (name "unconnected-(MOD1-BRIDGE_SPI_NSS-Pad14)") (class "Default")
      (node (ref "MOD1") (pin "14") (pinfunction "BRIDGE_SPI_NSS_14") (pintype "passive"))
    )
    (net (code "75") (name "unconnected-(MOD1-BRIDGE_UART_CTS-Pad2)") (class "Default")
      (node (ref "MOD1") (pin "2") (pinfunction "BRIDGE_UART_CTS_2") (pintype "passive"))
    )
    (net (code "76") (name "unconnected-(MOD1-BRIDGE_UART_RTS-Pad3)") (class "Default")
      (node (ref "MOD1") (pin "3") (pinfunction "BRIDGE_UART_RTS_3") (pintype "passive"))
    )
    (net (code "77") (name "unconnected-(MOD1-BRIDGE_UART_RX-Pad1)") (class "Default")
      (node (ref "MOD1") (pin "1") (pinfunction "BRIDGE_UART_RX_1") (pintype "passive"))
    )
    (net (code "78") (name "unconnected-(MOD1-BRIDGE_UART_TX-Pad11)") (class "Default")
      (node (ref "MOD1") (pin "11") (pinfunction "BRIDGE_UART_TX_11") (pintype "passive"))
    )
    (net (code "79") (name "unconnected-(MOD1-T_JTDI{slash}NC-Pad28)") (class "Default")
      (node (ref "MOD1") (pin "28") (pinfunction "T_JTDI/NC_28") (pintype "passive"))
    )
    (net (code "80") (name "unconnected-(MOD1-T_JTDO{slash}T_SWO-Pad6)") (class "Default")
      (node (ref "MOD1") (pin "6") (pinfunction "T_JTDO/T_SWO_6") (pintype "passive"))
    )
    (net (code "81") (name "unconnected-(MOD1-T_SW_DIR-Pad32)") (class "Default")
      (node (ref "MOD1") (pin "32") (pinfunction "T_SW_DIR_32") (pintype "passive"))
    )
    (net (code "82") (name "unconnected-(P1-Pad13)") (class "Default")
      (node (ref "P1") (pin "13") (pinfunction "13_13") (pintype "passive"))
    )
    (net (code "83") (name "unconnected-(P1-Pad14)") (class "Default")
      (node (ref "P1") (pin "14") (pinfunction "14_14") (pintype "passive"))
    )
    (net (code "84") (name "unconnected-(P2-Pad7)") (class "Default")
      (node (ref "P2") (pin "7") (pinfunction "7_7") (pintype "passive"))
    )
    (net (code "85") (name "unconnected-(P2-Pad8)") (class "Default")
      (node (ref "P2") (pin "8") (pinfunction "8_8") (pintype "passive"))
    )
    (net (code "86") (name "unconnected-(P3-Pad15)") (class "Default")
      (node (ref "P3") (pin "15") (pinfunction "15_15") (pintype "passive"))
    )
    (net (code "87") (name "unconnected-(U1-PB0-Pad26)") (class "Default")
      (node (ref "U1") (pin "26") (pinfunction "PB0_26") (pintype "bidirectional"))
    )
    (net (code "88") (name "unconnected-(U1-PB1-Pad27)") (class "Default")
      (node (ref "U1") (pin "27") (pinfunction "PB1_27") (pintype "bidirectional"))
    )
    (net (code "89") (name "unconnected-(U1-PB2-BOOT1(PB2)-Pad28)") (class "Default")
      (node (ref "U1") (pin "28") (pinfunction "PB2-BOOT1(PB2)_28") (pintype "bidirectional"))
    )
    (net (code "90") (name "unconnected-(U1-PB5-Pad57)") (class "Default")
      (node (ref "U1") (pin "57") (pinfunction "PB5_57") (pintype "bidirectional"))
    )
    (net (code "91") (name "unconnected-(U1-PB6-Pad58)") (class "Default")
      (node (ref "U1") (pin "58") (pinfunction "PB6_58") (pintype "bidirectional"))
    )
    (net (code "92") (name "unconnected-(U1-PB7-Pad59)") (class "Default")
      (node (ref "U1") (pin "59") (pinfunction "PB7_59") (pintype "bidirectional"))
    )
    (net (code "93") (name "unconnected-(U1-PB10-Pad29)") (class "Default")
      (node (ref "U1") (pin "29") (pinfunction "PB10_29") (pintype "bidirectional"))
    )
    (net (code "94") (name "unconnected-(U1-PB11-Pad30)") (class "Default")
      (node (ref "U1") (pin "30") (pinfunction "PB11_30") (pintype "bidirectional"))
    )
    (net (code "95") (name "unconnected-(U1-PB12-Pad33)") (class "Default")
      (node (ref "U1") (pin "33") (pinfunction "PB12_33") (pintype "bidirectional+no_connect"))
    )
    (net (code "96") (name "unconnected-(U1-PB13-Pad34)") (class "Default")
      (node (ref "U1") (pin "34") (pinfunction "PB13_34") (pintype "bidirectional+no_connect"))
    )
    (net (code "97") (name "unconnected-(U1-PB14-Pad35)") (class "Default")
      (node (ref "U1") (pin "35") (pinfunction "PB14_35") (pintype "bidirectional+no_connect"))
    )
    (net (code "98") (name "unconnected-(U1-PC2-Pad10)") (class "Default")
      (node (ref "U1") (pin "10") (pinfunction "PC2_10") (pintype "bidirectional"))
    )
    (net (code "99") (name "unconnected-(U1-PC5-Pad25)") (class "Default")
      (node (ref "U1") (pin "25") (pinfunction "PC5_25") (pintype "bidirectional"))
    )
    (net (code "100") (name "unconnected-(U1-PC6-Pad37)") (class "Default")
      (node (ref "U1") (pin "37") (pinfunction "PC6_37") (pintype "bidirectional+no_connect"))
    )
    (net (code "101") (name "unconnected-(U1-PC7-Pad38)") (class "Default")
      (node (ref "U1") (pin "38") (pinfunction "PC7_38") (pintype "bidirectional+no_connect"))
    )
    (net (code "102") (name "unconnected-(U1-PC8-Pad39)") (class "Default")
      (node (ref "U1") (pin "39") (pinfunction "PC8_39") (pintype "bidirectional"))
    )
    (net (code "103") (name "unconnected-(U1-PC9-Pad40)") (class "Default")
      (node (ref "U1") (pin "40") (pinfunction "PC9_40") (pintype "bidirectional"))
    )
    (net (code "104") (name "unconnected-(U1-PC10-Pad51)") (class "Default")
      (node (ref "U1") (pin "51") (pinfunction "PC10_51") (pintype "bidirectional"))
    )
    (net (code "105") (name "unconnected-(U1-PC11-Pad52)") (class "Default")
      (node (ref "U1") (pin "52") (pinfunction "PC11_52") (pintype "bidirectional"))
    )
    (net (code "106") (name "unconnected-(U1-PC12-Pad53)") (class "Default")
      (node (ref "U1") (pin "53") (pinfunction "PC12_53") (pintype "bidirectional"))
    )
    (net (code "107") (name "unconnected-(U1-PC13-Pad2)") (class "Default")
      (node (ref "U1") (pin "2") (pinfunction "PC13_2") (pintype "bidirectional"))
    )
    (net (code "108") (name "unconnected-(U1-PC14-OSC32_IN(PC14)-Pad3)") (class "Default")
      (node (ref "U1") (pin "3") (pinfunction "PC14-OSC32_IN(PC14)_3") (pintype "bidirectional"))
    )
    (net (code "109") (name "unconnected-(U1-PC15-OSC32_OUT(PC15)-Pad4)") (class "Default")
      (node (ref "U1") (pin "4") (pinfunction "PC15-OSC32_OUT(PC15)_4") (pintype "bidirectional"))
    )
    (net (code "110") (name "unconnected-(U1-PD2-Pad54)") (class "Default")
      (node (ref "U1") (pin "54") (pinfunction "PD2_54") (pintype "bidirectional"))
    )
    (net (code "111") (name "unconnected-(U1-PH1-OSC_OUT(PH1)-Pad6)") (class "Default")
      (node (ref "U1") (pin "6") (pinfunction "PH1-OSC_OUT(PH1)_6") (pintype "bidirectional+no_connect"))
    )
    (net (code "112") (name "unconnected-(U2-SPLIT-Pad5)") (class "Default")
      (node (ref "U2") (pin "5") (pinfunction "SPLIT_5") (pintype "passive"))
    )
    (net (code "113") (name "unconnected-(Y1-TRI-STATE-Pad1)") (class "Default")
      (node (ref "Y1") (pin "1") (pinfunction "TRI-STATE_1") (pintype "input+no_connect"))
    )
  )
)
